# ESP32_C3_MotorDriver.net
KiCad netlist of a schematic drawn in EAGLE
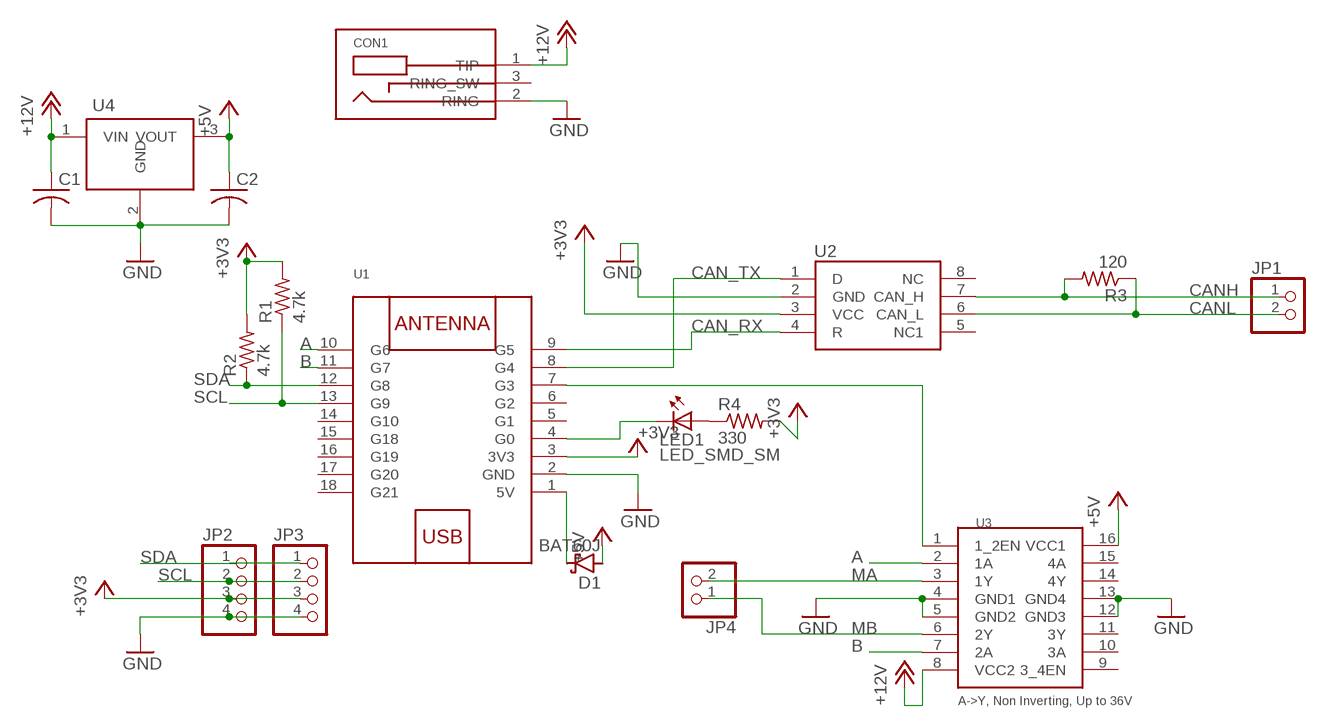
[diagram p0: schematic, sheet 1]

(export (version "E")
  (design (tool "Eeschema 10.0.6"))
  (components
    (comp (ref "C1")
      (value "C-USC0805")
      (footprint "eagle-import:C0805")
      (libsource (lib "eagle-import") (part "C-USC0805"))
    )
    (comp (ref "C2")
      (value "C-USC0805")
      (footprint "eagle-import:C0805")
      (libsource (lib "eagle-import") (part "C-USC0805"))
    )
    (comp (ref "CON1")
      (value "BARREL_JACK_3PINPJ-102A_2MM_HOLES")
      (footprint "eagle-import:PJ-102A_2MM_HOLES")
      (libsource (lib "eagle-import") (part "BARREL_JACK_3PINPJ-102A_2MM_HOLES"))
    )
    (comp (ref "D1")
      (value "BAT60J")
      (footprint "eagle-import:SOD323_ST")
      (libsource (lib "eagle-import") (part "BAT60J"))
    )
    (comp (ref "JP1")
      (value "PINHD-1X2")
      (footprint "eagle-import:1X02")
      (libsource (lib "eagle-import") (part "PINHD-1X2"))
    )
    (comp (ref "JP2")
      (value "PINHD-1X4")
      (footprint "eagle-import:1X04")
      (libsource (lib "eagle-import") (part "PINHD-1X4"))
    )
    (comp (ref "JP3")
      (value "PINHD-1X4")
      (footprint "eagle-import:1X04")
      (libsource (lib "eagle-import") (part "PINHD-1X4"))
    )
    (comp (ref "JP4")
      (value "PINHD-1X2")
      (footprint "eagle-import:1X02")
      (libsource (lib "eagle-import") (part "PINHD-1X2"))
    )
    (comp (ref "LED1")
      (value "LED_SMD_SM")
      (footprint "eagle-import:LED_SMD_SM")
      (libsource (lib "eagle-import") (part "LED_SMD_SM"))
    )
    (comp (ref "R1")
      (value "4.7k")
      (footprint "eagle-import:M0805")
      (libsource (lib "eagle-import") (part "R-US_M0805"))
    )
    (comp (ref "R2")
      (value "4.7k")
      (footprint "eagle-import:M0805")
      (libsource (lib "eagle-import") (part "R-US_M0805"))
    )
    (comp (ref "R3")
      (value "120")
      (footprint "eagle-import:M0805")
      (libsource (lib "eagle-import") (part "R-US_M0805"))
    )
    (comp (ref "R4")
      (value "330")
      (footprint "eagle-import:M0805")
      (libsource (lib "eagle-import") (part "R-US_M0805"))
    )
    (comp (ref "U1")
      (value "ESP32C3ZERO")
      (footprint "eagle-import:ESP32SUPERMINI_ESP32-SUPERMINI")
      (libsource (lib "eagle-import") (part "ESP32C3ZERO"))
    )
    (comp (ref "U2")
      (value "SN65HVD232DSOIC8")
      (footprint "eagle-import:SOIC-8")
      (libsource (lib "eagle-import") (part "SN65HVD232DSOIC8"))
    )
    (comp (ref "U3")
      (value "L293DDIP16")
      (footprint "eagle-import:DIP16_7.62MM")
      (libsource (lib "eagle-import") (part "L293DDIP16"))
    )
    (comp (ref "U4")
      (value "7805")
      (footprint "eagle-import:TO252-3")
      (libsource (lib "eagle-import") (part "7805"))
    )
  )
  (nets
    (net (code "1") (name "+3V3") (class "Default")
      (node (ref "JP2") (pin "3") (pinfunction "3_3") (pintype "passive"))
      (node (ref "JP3") (pin "3") (pinfunction "3_3") (pintype "passive"))
      (node (ref "R1") (pin "2") (pinfunction "2_2") (pintype "passive"))
      (node (ref "R2") (pin "2") (pinfunction "2_2") (pintype "passive"))
      (node (ref "R4") (pin "2") (pinfunction "2_2") (pintype "passive"))
      (node (ref "U1") (pin "3") (pinfunction "3V3_3") (pintype "bidirectional"))
      (node (ref "U2") (pin "3") (pinfunction "VCC_3") (pintype "bidirectional"))
    )
    (net (code "2") (name "+5V") (class "Default")
      (node (ref "C2") (pin "1") (pinfunction "1_1") (pintype "passive"))
      (node (ref "D1") (pin "A") (pinfunction "A_A") (pintype "passive"))
      (node (ref "U3") (pin "16") (pinfunction "VCC1_16") (pintype "bidirectional"))
      (node (ref "U4") (pin "3") (pinfunction "VOUT_3") (pintype "bidirectional"))
    )
    (net (code "3") (name "+12V") (class "Default")
      (node (ref "C1") (pin "1") (pinfunction "1_1") (pintype "passive"))
      (node (ref "CON1") (pin "1") (pinfunction "TIP_1") (pintype "bidirectional"))
      (node (ref "U3") (pin "8") (pinfunction "VCC2_8") (pintype "bidirectional"))
      (node (ref "U4") (pin "1") (pinfunction "VIN_1") (pintype "bidirectional"))
    )
    (net (code "4") (name "/A") (class "Default")
      (node (ref "U1") (pin "10") (pinfunction "G6_10") (pintype "bidirectional"))
      (node (ref "U3") (pin "2") (pinfunction "1A_2") (pintype "bidirectional"))
    )
    (net (code "5") (name "/B") (class "Default")
      (node (ref "U1") (pin "11") (pinfunction "G7_11") (pintype "bidirectional"))
      (node (ref "U3") (pin "7") (pinfunction "2A_7") (pintype "bidirectional"))
    )
    (net (code "6") (name "/CANH") (class "Default")
      (node (ref "JP1") (pin "1") (pinfunction "1_1") (pintype "passive"))
      (node (ref "R3") (pin "2") (pinfunction "2_2") (pintype "passive"))
      (node (ref "U2") (pin "7") (pinfunction "CAN_H_7") (pintype "bidirectional"))
    )
    (net (code "7") (name "/CANL") (class "Default")
      (node (ref "JP1") (pin "2") (pinfunction "2_2") (pintype "passive"))
      (node (ref "R3") (pin "1") (pinfunction "1_1") (pintype "passive"))
      (node (ref "U2") (pin "6") (pinfunction "CAN_L_6") (pintype "bidirectional"))
    )
    (net (code "8") (name "/CAN_RX") (class "Default")
      (node (ref "U1") (pin "9") (pinfunction "G5_9") (pintype "bidirectional"))
      (node (ref "U2") (pin "4") (pinfunction "R_4") (pintype "bidirectional"))
    )
    (net (code "9") (name "/CAN_TX") (class "Default")
      (node (ref "U1") (pin "8") (pinfunction "G4_8") (pintype "bidirectional"))
      (node (ref "U2") (pin "1") (pinfunction "D_1") (pintype "bidirectional"))
    )
    (net (code "10") (name "/G19") (class "Default")
      (node (ref "U1") (pin "16") (pinfunction "G19_16") (pintype "power_in"))
    )
    (net (code "11") (name "/MA") (class "Default")
      (node (ref "JP4") (pin "2") (pinfunction "2_2") (pintype "passive"))
      (node (ref "U3") (pin "3") (pinfunction "1Y_3") (pintype "bidirectional"))
    )
    (net (code "12") (name "/MB") (class "Default")
      (node (ref "JP4") (pin "1") (pinfunction "1_1") (pintype "passive"))
      (node (ref "U3") (pin "6") (pinfunction "2Y_6") (pintype "bidirectional"))
    )
    (net (code "13") (name "/SCL") (class "Default")
      (node (ref "JP2") (pin "2") (pinfunction "2_2") (pintype "passive"))
      (node (ref "JP3") (pin "2") (pinfunction "2_2") (pintype "passive"))
      (node (ref "R1") (pin "1") (pinfunction "1_1") (pintype "passive"))
      (node (ref "U1") (pin "13") (pinfunction "G9_13") (pintype "bidirectional"))
    )
    (net (code "14") (name "/SDA") (class "Default")
      (node (ref "JP2") (pin "1") (pinfunction "1_1") (pintype "passive"))
      (node (ref "JP3") (pin "1") (pinfunction "1_1") (pintype "passive"))
      (node (ref "R2") (pin "1") (pinfunction "1_1") (pintype "passive"))
      (node (ref "U1") (pin "12") (pinfunction "G8_12") (pintype "bidirectional"))
    )
    (net (code "15") (name "GND") (class "Default")
      (node (ref "C1") (pin "2") (pinfunction "2_2") (pintype "passive"))
      (node (ref "C2") (pin "2") (pinfunction "2_2") (pintype "passive"))
      (node (ref "CON1") (pin "2") (pinfunction "RING_2") (pintype "bidirectional"))
      (node (ref "JP2") (pin "4") (pinfunction "4_4") (pintype "passive"))
      (node (ref "JP3") (pin "4") (pinfunction "4_4") (pintype "passive"))
      (node (ref "U1") (pin "2") (pinfunction "GND_2") (pintype "power_in"))
      (node (ref "U2") (pin "2") (pinfunction "GND_2") (pintype "bidirectional"))
      (node (ref "U3") (pin "12") (pinfunction "GND3_12") (pintype "bidirectional"))
      (node (ref "U3") (pin "13") (pinfunction "GND4_13") (pintype "bidirectional"))
      (node (ref "U3") (pin "4") (pinfunction "GND1_4") (pintype "bidirectional"))
      (node (ref "U3") (pin "5") (pinfunction "GND2_5") (pintype "bidirectional"))
      (node (ref "U4") (pin "2") (pinfunction "GND_2") (pintype "bidirectional"))
    )
    (net (code "16") (name "Net-(LED1-A)") (class "Default")
      (node (ref "LED1") (pin "1") (pinfunction "A_1") (pintype "passive"))
      (node (ref "R4") (pin "1") (pinfunction "1_1") (pintype "passive"))
    )
    (net (code "17") (name "Net-(LED1-C)") (class "Default")
      (node (ref "LED1") (pin "2") (pinfunction "C_2") (pintype "passive"))
      (node (ref "U1") (pin "4") (pinfunction "G0_4") (pintype "bidirectional"))
    )
    (net (code "18") (name "Net-(U1-5V)") (class "Default")
      (node (ref "D1") (pin "C") (pinfunction "C_C") (pintype "passive"))
      (node (ref "U1") (pin "1") (pinfunction "5V_1") (pintype "power_in"))
    )
    (net (code "19") (name "Net-(U1-G3)") (class "Default")
      (node (ref "U1") (pin "7") (pinfunction "G3_7") (pintype "bidirectional"))
      (node (ref "U3") (pin "1") (pinfunction "1_2EN_1") (pintype "bidirectional"))
    )
    (net (code "20") (name "unconnected-(CON1-RING_SW-Pad3)") (class "Default")
      (node (ref "CON1") (pin "3") (pinfunction "RING_SW_3") (pintype "bidirectional"))
    )
    (net (code "21") (name "unconnected-(U1-G1-Pad5)") (class "Default")
      (node (ref "U1") (pin "5") (pinfunction "G1_5") (pintype "bidirectional"))
    )
    (net (code "22") (name "unconnected-(U1-G2-Pad6)") (class "Default")
      (node (ref "U1") (pin "6") (pinfunction "G2_6") (pintype "bidirectional"))
    )
    (net (code "23") (name "unconnected-(U1-G10-Pad14)") (class "Default")
      (node (ref "U1") (pin "14") (pinfunction "G10_14") (pintype "bidirectional"))
    )
    (net (code "24") (name "unconnected-(U1-G18-Pad15)") (class "Default")
      (node (ref "U1") (pin "15") (pinfunction "G18_15") (pintype "bidirectional"))
    )
    (net (code "25") (name "unconnected-(U1-G20-Pad17)") (class "Default")
      (node (ref "U1") (pin "17") (pinfunction "G20_17") (pintype "bidirectional"))
    )
    (net (code "26") (name "unconnected-(U1-G21-Pad18)") (class "Default")
      (node (ref "U1") (pin "18") (pinfunction "G21_18") (pintype "bidirectional"))
    )
    (net (code "27") (name "unconnected-(U2-NC-Pad8)") (class "Default")
      (node (ref "U2") (pin "8") (pinfunction "NC_8") (pintype "bidirectional"))
    )
    (net (code "28") (name "unconnected-(U2-NC1-Pad5)") (class "Default")
      (node (ref "U2") (pin "5") (pinfunction "NC1_5") (pintype "bidirectional"))
    )
    (net (code "29") (name "unconnected-(U3-3A-Pad10)") (class "Default")
      (node (ref "U3") (pin "10") (pinfunction "3A_10") (pintype "bidirectional"))
    )
    (net (code "30") (name "unconnected-(U3-3Y-Pad11)") (class "Default")
      (node (ref "U3") (pin "11") (pinfunction "3Y_11") (pintype "bidirectional"))
    )
    (net (code "31") (name "unconnected-(U3-3_4EN-Pad9)") (class "Default")
      (node (ref "U3") (pin "9") (pinfunction "3_4EN_9") (pintype "bidirectional"))
    )
    (net (code "32") (name "unconnected-(U3-4A-Pad15)") (class "Default")
      (node (ref "U3") (pin "15") (pinfunction "4A_15") (pintype "bidirectional"))
    )
    (net (code "33") (name "unconnected-(U3-4Y-Pad14)") (class "Default")
      (node (ref "U3") (pin "14") (pinfunction "4Y_14") (pintype "bidirectional"))
    )
  )
)
